# LTC2949.net
KiCad netlist of a schematic drawn in Altium Designer
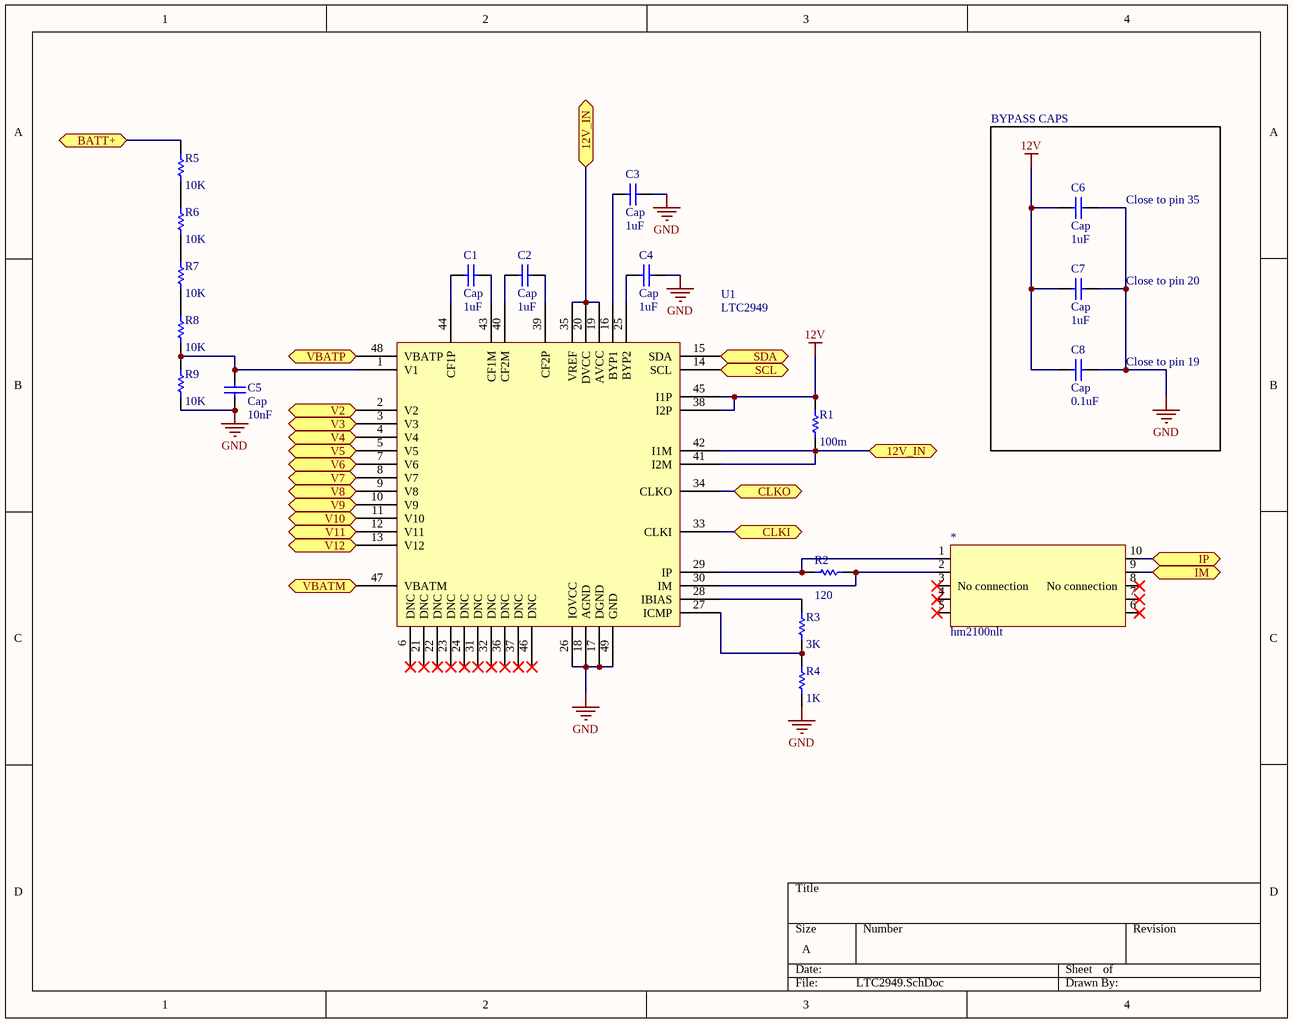
[diagram p0: LTC2949.SchDoc]

(export (version "E")
  (design (tool "Eeschema 10.0.6"))
  (components
    (comp (ref "*") (value "hm2100nlt") (libsource (lib "TestBoard") (part "hm2100nlt")))
    (comp (ref "C1")
      (value "Cap")
      (footprint "RAD-0.3")
      (description "Capacitor")
      (fields (field (name "ALTIUM_VALUE") "1uF") (field (name "PUBLISHER") "Altium Limited"))
      (libsource (lib "Miscellaneous Devices") (part "Cap"))
    )
    (comp (ref "C2")
      (value "Cap")
      (footprint "RAD-0.3")
      (description "Capacitor")
      (fields (field (name "ALTIUM_VALUE") "1uF") (field (name "PUBLISHER") "Altium Limited"))
      (libsource (lib "Miscellaneous Devices") (part "Cap"))
    )
    (comp (ref "C3")
      (value "Cap")
      (footprint "RAD-0.3")
      (description "Capacitor")
      (fields (field (name "ALTIUM_VALUE") "1uF") (field (name "PUBLISHER") "Altium Limited"))
      (libsource (lib "Miscellaneous Devices") (part "Cap"))
    )
    (comp (ref "C4")
      (value "Cap")
      (footprint "RAD-0.3")
      (description "Capacitor")
      (fields (field (name "ALTIUM_VALUE") "1uF") (field (name "PUBLISHER") "Altium Limited"))
      (libsource (lib "Miscellaneous Devices") (part "Cap"))
    )
    (comp (ref "C5")
      (value "Cap")
      (footprint "RAD-0.3")
      (description "Capacitor")
      (fields (field (name "ALTIUM_VALUE") "10nF") (field (name "PUBLISHER") "Altium Limited"))
      (libsource (lib "Miscellaneous Devices") (part "Cap"))
    )
    (comp (ref "C6")
      (value "Cap")
      (footprint "RAD-0.3")
      (description "Capacitor")
      (fields (field (name "ALTIUM_VALUE") "1uF") (field (name "PUBLISHER") "Altium Limited"))
      (libsource (lib "Miscellaneous Devices") (part "Cap"))
    )
    (comp (ref "C7")
      (value "Cap")
      (footprint "RAD-0.3")
      (description "Capacitor")
      (fields (field (name "ALTIUM_VALUE") "1uF") (field (name "PUBLISHER") "Altium Limited"))
      (libsource (lib "Miscellaneous Devices") (part "Cap"))
    )
    (comp (ref "C8")
      (value "Cap")
      (footprint "RAD-0.3")
      (description "Capacitor")
      (fields (field (name "ALTIUM_VALUE") "0.1uF") (field (name "PUBLISHER") "Altium Limited"))
      (libsource (lib "Miscellaneous Devices") (part "Cap"))
    )
    (comp (ref "R1")
      (value "100m")
      (footprint "AXIAL-0.3")
      (description "Resistor")
      (fields (field (name "Comment") "Res1") (field (name "PUBLISHER") "Altium Limited"))
      (libsource (lib "Miscellaneous Devices") (part "Res1"))
    )
    (comp (ref "R2")
      (value "120")
      (footprint "AXIAL-0.3")
      (description "Resistor")
      (fields (field (name "Comment") "1%") (field (name "PUBLISHER") "Altium Limited"))
      (libsource (lib "Miscellaneous Devices") (part "Res1"))
    )
    (comp (ref "R3")
      (value "3K")
      (footprint "AXIAL-0.3")
      (description "Resistor")
      (fields (field (name "Comment") "1%") (field (name "PUBLISHER") "Altium Limited"))
      (libsource (lib "Miscellaneous Devices") (part "Res1"))
    )
    (comp (ref "R4")
      (value "1K")
      (footprint "AXIAL-0.3")
      (description "Resistor")
      (fields (field (name "Comment") "1%") (field (name "PUBLISHER") "Altium Limited"))
      (libsource (lib "Miscellaneous Devices") (part "Res1"))
    )
    (comp (ref "R5")
      (value "10K")
      (footprint "AXIAL-0.3")
      (description "Resistor")
      (fields (field (name "Comment") "Res1") (field (name "PUBLISHER") "Altium Limited"))
      (libsource (lib "Miscellaneous Devices") (part "Res1"))
    )
    (comp (ref "R6")
      (value "10K")
      (footprint "AXIAL-0.3")
      (description "Resistor")
      (fields (field (name "Comment") "Res1") (field (name "PUBLISHER") "Altium Limited"))
      (libsource (lib "Miscellaneous Devices") (part "Res1"))
    )
    (comp (ref "R7")
      (value "10K")
      (footprint "AXIAL-0.3")
      (description "Resistor")
      (fields (field (name "Comment") "Res1") (field (name "PUBLISHER") "Altium Limited"))
      (libsource (lib "Miscellaneous Devices") (part "Res1"))
    )
    (comp (ref "R8")
      (value "10K")
      (footprint "AXIAL-0.3")
      (description "Resistor")
      (fields (field (name "Comment") "Res1") (field (name "PUBLISHER") "Altium Limited"))
      (libsource (lib "Miscellaneous Devices") (part "Res1"))
    )
    (comp (ref "R9")
      (value "10K")
      (footprint "AXIAL-0.3")
      (description "Resistor")
      (fields (field (name "Comment") "Res1") (field (name "PUBLISHER") "Altium Limited"))
      (libsource (lib "Miscellaneous Devices") (part "Res1"))
    )
    (comp (ref "U1") (value "LTC2949") (libsource (lib "TestBoard") (part "LTC2949")))
  )
  (nets
    (net (code "1") (name "/12V_IN") (class "Default")
      (node (ref "R1") (pin "1") (pinfunction "1_1") (pintype "passive"))
      (node (ref "U1") (pin "19") (pinfunction "AVCC_19") (pintype "power_in"))
      (node (ref "U1") (pin "20") (pinfunction "DVCC_20") (pintype "power_in"))
      (node (ref "U1") (pin "35") (pinfunction "VREF_35") (pintype "power_in"))
      (node (ref "U1") (pin "41") (pinfunction "I2M_41") (pintype "passive"))
      (node (ref "U1") (pin "42") (pinfunction "I1M_42") (pintype "passive"))
    )
    (net (code "2") (name "/BATT+") (class "Default")
      (node (ref "R5") (pin "2") (pinfunction "2_2") (pintype "passive"))
    )
    (net (code "3") (name "/CLKI") (class "Default")
      (node (ref "U1") (pin "33") (pinfunction "CLKI_33") (pintype "passive"))
    )
    (net (code "4") (name "/CLKO") (class "Default")
      (node (ref "U1") (pin "34") (pinfunction "CLKO_34") (pintype "passive"))
    )
    (net (code "5") (name "/IM") (class "Default") (node (ref "*") (pin "9") (pintype "passive")))
    (net (code "6") (name "/IP") (class "Default") (node (ref "*") (pin "10") (pintype "passive")))
    (net (code "7") (name "/SCL") (class "Default")
      (node (ref "U1") (pin "14") (pinfunction "SCL_14") (pintype "passive"))
    )
    (net (code "8") (name "/SDA") (class "Default")
      (node (ref "U1") (pin "15") (pinfunction "SDA_15") (pintype "passive"))
    )
    (net (code "9") (name "/V2") (class "Default")
      (node (ref "U1") (pin "2") (pinfunction "V2_2") (pintype "passive"))
    )
    (net (code "10") (name "/V3") (class "Default")
      (node (ref "U1") (pin "3") (pinfunction "V3_3") (pintype "passive"))
    )
    (net (code "11") (name "/V4") (class "Default")
      (node (ref "U1") (pin "4") (pinfunction "V4_4") (pintype "passive"))
    )
    (net (code "12") (name "/V5") (class "Default")
      (node (ref "U1") (pin "5") (pinfunction "V5_5") (pintype "passive"))
    )
    (net (code "13") (name "/V6") (class "Default")
      (node (ref "U1") (pin "7") (pinfunction "V6_7") (pintype "passive"))
    )
    (net (code "14") (name "/V7") (class "Default")
      (node (ref "U1") (pin "8") (pinfunction "V7_8") (pintype "passive"))
    )
    (net (code "15") (name "/V8") (class "Default")
      (node (ref "U1") (pin "9") (pinfunction "V8_9") (pintype "passive"))
    )
    (net (code "16") (name "/V9") (class "Default")
      (node (ref "U1") (pin "10") (pinfunction "V9_10") (pintype "passive"))
    )
    (net (code "17") (name "/V10") (class "Default")
      (node (ref "U1") (pin "11") (pinfunction "V10_11") (pintype "passive"))
    )
    (net (code "18") (name "/V11") (class "Default")
      (node (ref "U1") (pin "12") (pinfunction "V11_12") (pintype "passive"))
    )
    (net (code "19") (name "/V12") (class "Default")
      (node (ref "U1") (pin "13") (pinfunction "V12_13") (pintype "passive"))
    )
    (net (code "20") (name "/VBATM") (class "Default")
      (node (ref "U1") (pin "47") (pinfunction "VBATM_47") (pintype "passive"))
    )
    (net (code "21") (name "/VBATP") (class "Default")
      (node (ref "U1") (pin "48") (pinfunction "VBATP_48") (pintype "passive"))
    )
    (net (code "22") (name "12V") (class "Default")
      (node (ref "C6") (pin "1") (pinfunction "1_1") (pintype "passive"))
      (node (ref "C7") (pin "1") (pinfunction "1_1") (pintype "passive"))
      (node (ref "C8") (pin "1") (pinfunction "1_1") (pintype "passive"))
      (node (ref "R1") (pin "2") (pinfunction "2_2") (pintype "passive"))
      (node (ref "U1") (pin "38") (pinfunction "I2P_38") (pintype "passive"))
      (node (ref "U1") (pin "45") (pinfunction "I1P_45") (pintype "passive"))
    )
    (net (code "23") (name "GND") (class "Default")
      (node (ref "C3") (pin "2") (pinfunction "2_2") (pintype "passive"))
      (node (ref "C4") (pin "2") (pinfunction "2_2") (pintype "passive"))
      (node (ref "C5") (pin "1") (pinfunction "1_1") (pintype "passive"))
      (node (ref "C6") (pin "2") (pinfunction "2_2") (pintype "passive"))
      (node (ref "C7") (pin "2") (pinfunction "2_2") (pintype "passive"))
      (node (ref "C8") (pin "2") (pinfunction "2_2") (pintype "passive"))
      (node (ref "R4") (pin "2") (pinfunction "2_2") (pintype "passive"))
      (node (ref "R9") (pin "1") (pinfunction "1_1") (pintype "passive"))
      (node (ref "U1") (pin "17") (pinfunction "DGND_17") (pintype "power_in"))
      (node (ref "U1") (pin "18") (pinfunction "AGND_18") (pintype "power_in"))
      (node (ref "U1") (pin "26") (pinfunction "IOVCC_26") (pintype "power_in"))
      (node (ref "U1") (pin "49") (pinfunction "GND_49") (pintype "power_in"))
    )
    (net (code "24") (name "Net-(R5-Pad1)") (class "Default")
      (node (ref "R5") (pin "1") (pinfunction "1_1") (pintype "passive"))
      (node (ref "R6") (pin "2") (pinfunction "2_2") (pintype "passive"))
    )
    (net (code "25") (name "Net-(R6-Pad1)") (class "Default")
      (node (ref "R6") (pin "1") (pinfunction "1_1") (pintype "passive"))
      (node (ref "R7") (pin "2") (pinfunction "2_2") (pintype "passive"))
    )
    (net (code "26") (name "Net-(R7-Pad1)") (class "Default")
      (node (ref "R7") (pin "1") (pinfunction "1_1") (pintype "passive"))
      (node (ref "R8") (pin "2") (pinfunction "2_2") (pintype "passive"))
    )
    (net (code "27") (name "Net-(U1-BYP1)") (class "Default")
      (node (ref "C3") (pin "1") (pinfunction "1_1") (pintype "passive"))
      (node (ref "U1") (pin "16") (pinfunction "BYP1_16") (pintype "power_in"))
    )
    (net (code "28") (name "Net-(U1-BYP2)") (class "Default")
      (node (ref "C4") (pin "1") (pinfunction "1_1") (pintype "passive"))
      (node (ref "U1") (pin "25") (pinfunction "BYP2_25") (pintype "power_in"))
    )
    (net (code "29") (name "Net-(U1-CF1M)") (class "Default")
      (node (ref "C1") (pin "2") (pinfunction "2_2") (pintype "passive"))
      (node (ref "U1") (pin "43") (pinfunction "CF1M_43") (pintype "passive"))
    )
    (net (code "30") (name "Net-(U1-CF1P)") (class "Default")
      (node (ref "C1") (pin "1") (pinfunction "1_1") (pintype "passive"))
      (node (ref "U1") (pin "44") (pinfunction "CF1P_44") (pintype "passive"))
    )
    (net (code "31") (name "Net-(U1-CF2M)") (class "Default")
      (node (ref "C2") (pin "1") (pinfunction "1_1") (pintype "passive"))
      (node (ref "U1") (pin "40") (pinfunction "CF2M_40") (pintype "passive"))
    )
    (net (code "32") (name "Net-(U1-CF2P)") (class "Default")
      (node (ref "C2") (pin "2") (pinfunction "2_2") (pintype "passive"))
      (node (ref "U1") (pin "39") (pinfunction "CF2P_39") (pintype "passive"))
    )
    (net (code "33") (name "Net-(U1-IBIAS)") (class "Default")
      (node (ref "R3") (pin "2") (pinfunction "2_2") (pintype "passive"))
      (node (ref "U1") (pin "28") (pinfunction "IBIAS_28") (pintype "passive"))
    )
    (net (code "34") (name "Net-(U1-ICMP)") (class "Default")
      (node (ref "R3") (pin "1") (pinfunction "1_1") (pintype "passive"))
      (node (ref "R4") (pin "1") (pinfunction "1_1") (pintype "passive"))
      (node (ref "U1") (pin "27") (pinfunction "ICMP_27") (pintype "passive"))
    )
    (net (code "35") (name "Net-(U1-IM)") (class "Default")
      (node (ref "*") (pin "2") (pintype "passive"))
      (node (ref "R2") (pin "2") (pinfunction "2_2") (pintype "passive"))
      (node (ref "U1") (pin "30") (pinfunction "IM_30") (pintype "passive"))
    )
    (net (code "36") (name "Net-(U1-IP)") (class "Default")
      (node (ref "*") (pin "1") (pintype "passive"))
      (node (ref "R2") (pin "1") (pinfunction "1_1") (pintype "passive"))
      (node (ref "U1") (pin "29") (pinfunction "IP_29") (pintype "passive"))
    )
    (net (code "37") (name "Net-(U1-V1)") (class "Default")
      (node (ref "C5") (pin "2") (pinfunction "2_2") (pintype "passive"))
      (node (ref "R8") (pin "1") (pinfunction "1_1") (pintype "passive"))
      (node (ref "R9") (pin "2") (pinfunction "2_2") (pintype "passive"))
      (node (ref "U1") (pin "1") (pinfunction "V1_1") (pintype "passive"))
    )
    (net (code "38") (name "unconnected-(*-No_connection-Pad3)") (class "Default")
      (node (ref "*") (pin "3") (pinfunction "No_connection_3") (pintype "passive+no_connect"))
    )
    (net (code "39") (name "unconnected-(*-No_connection-Pad8)") (class "Default")
      (node (ref "*") (pin "8") (pinfunction "No_connection_8") (pintype "passive+no_connect"))
    )
    (net (code "40") (name "unconnected-(*-Pad4)") (class "Default")
      (node (ref "*") (pin "4") (pintype "passive+no_connect"))
    )
    (net (code "41") (name "unconnected-(*-Pad5)") (class "Default")
      (node (ref "*") (pin "5") (pintype "passive+no_connect"))
    )
    (net (code "42") (name "unconnected-(*-Pad6)") (class "Default")
      (node (ref "*") (pin "6") (pintype "passive+no_connect"))
    )
    (net (code "43") (name "unconnected-(*-Pad7)") (class "Default")
      (node (ref "*") (pin "7") (pintype "passive+no_connect"))
    )
    (net (code "44") (name "unconnected-(U1-DNC-Pad6)") (class "Default")
      (node (ref "U1") (pin "6") (pinfunction "DNC_6") (pintype "passive+no_connect"))
    )
    (net (code "45") (name "unconnected-(U1-DNC-Pad21)") (class "Default")
      (node (ref "U1") (pin "21") (pinfunction "DNC_21") (pintype "passive+no_connect"))
    )
    (net (code "46") (name "unconnected-(U1-DNC-Pad22)") (class "Default")
      (node (ref "U1") (pin "22") (pinfunction "DNC_22") (pintype "passive+no_connect"))
    )
    (net (code "47") (name "unconnected-(U1-DNC-Pad23)") (class "Default")
      (node (ref "U1") (pin "23") (pinfunction "DNC_23") (pintype "passive+no_connect"))
    )
    (net (code "48") (name "unconnected-(U1-DNC-Pad24)") (class "Default")
      (node (ref "U1") (pin "24") (pinfunction "DNC_24") (pintype "passive+no_connect"))
    )
    (net (code "49") (name "unconnected-(U1-DNC-Pad31)") (class "Default")
      (node (ref "U1") (pin "31") (pinfunction "DNC_31") (pintype "passive+no_connect"))
    )
    (net (code "50") (name "unconnected-(U1-DNC-Pad32)") (class "Default")
      (node (ref "U1") (pin "32") (pinfunction "DNC_32") (pintype "passive+no_connect"))
    )
    (net (code "51") (name "unconnected-(U1-DNC-Pad36)") (class "Default")
      (node (ref "U1") (pin "36") (pinfunction "DNC_36") (pintype "passive+no_connect"))
    )
    (net (code "52") (name "unconnected-(U1-DNC-Pad37)") (class "Default")
      (node (ref "U1") (pin "37") (pinfunction "DNC_37") (pintype "passive+no_connect"))
    )
    (net (code "53") (name "unconnected-(U1-DNC-Pad46)") (class "Default")
      (node (ref "U1") (pin "46") (pinfunction "DNC_46") (pintype "passive+no_connect"))
    )
  )
)
